# sch_substrate_board_ethernet.net
KiCad netlist of a schematic drawn in Altium Designer
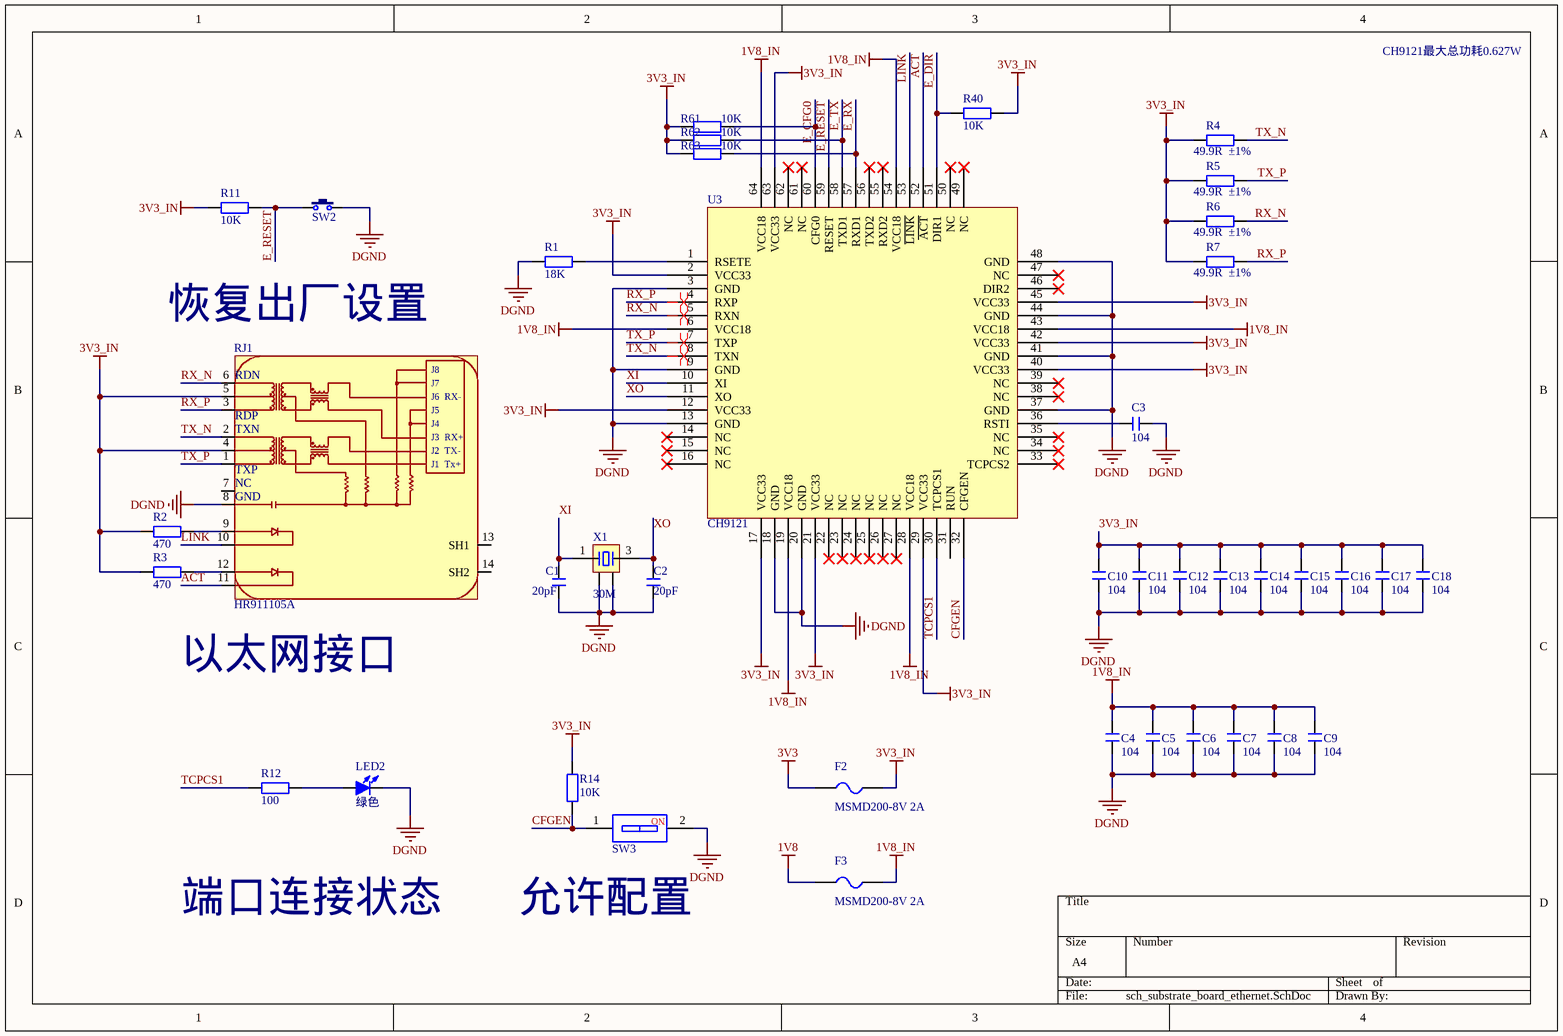
[diagram p0: sch_substrate_board_ethernet.SchDoc]

(export (version "E")
  (design (tool "Eeschema 10.0.6"))
  (components
    (comp (ref "C1")
      (value "20pF")
      (footprint "C 0805_L")
      (description "贴片电容")
      (libsource (lib "0.1 - 电阻-电容-电感") (part "C"))
    )
    (comp (ref "C2")
      (value "20pF")
      (footprint "C 0805_L")
      (description "贴片电容")
      (libsource (lib "0.1 - 电阻-电容-电感") (part "C"))
    )
    (comp (ref "C3")
      (value "104")
      (footprint "C 0805_L")
      (description "贴片电容")
      (libsource (lib "0.1 - 电阻-电容-电感") (part "C"))
    )
    (comp (ref "C4")
      (value "104")
      (footprint "C 0805_L")
      (description "贴片电容")
      (libsource (lib "0.1 - 电阻-电容-电感") (part "C"))
    )
    (comp (ref "C5")
      (value "104")
      (footprint "C 0805_L")
      (description "贴片电容")
      (libsource (lib "0.1 - 电阻-电容-电感") (part "C"))
    )
    (comp (ref "C6")
      (value "104")
      (footprint "C 0805_L")
      (description "贴片电容")
      (libsource (lib "0.1 - 电阻-电容-电感") (part "C"))
    )
    (comp (ref "C7")
      (value "104")
      (footprint "C 0805_L")
      (description "贴片电容")
      (libsource (lib "0.1 - 电阻-电容-电感") (part "C"))
    )
    (comp (ref "C8")
      (value "104")
      (footprint "C 0805_L")
      (description "贴片电容")
      (libsource (lib "0.1 - 电阻-电容-电感") (part "C"))
    )
    (comp (ref "C9")
      (value "104")
      (footprint "C 0805_L")
      (description "贴片电容")
      (libsource (lib "0.1 - 电阻-电容-电感") (part "C"))
    )
    (comp (ref "C10")
      (value "104")
      (footprint "C 0805_L")
      (description "贴片电容")
      (libsource (lib "0.1 - 电阻-电容-电感") (part "C"))
    )
    (comp (ref "C11")
      (value "104")
      (footprint "C 0805_L")
      (description "贴片电容")
      (libsource (lib "0.1 - 电阻-电容-电感") (part "C"))
    )
    (comp (ref "C12")
      (value "104")
      (footprint "C 0805_L")
      (description "贴片电容")
      (libsource (lib "0.1 - 电阻-电容-电感") (part "C"))
    )
    (comp (ref "C13")
      (value "104")
      (footprint "C 0805_L")
      (description "贴片电容")
      (libsource (lib "0.1 - 电阻-电容-电感") (part "C"))
    )
    (comp (ref "C14")
      (value "104")
      (footprint "C 0805_L")
      (description "贴片电容")
      (libsource (lib "0.1 - 电阻-电容-电感") (part "C"))
    )
    (comp (ref "C15")
      (value "104")
      (footprint "C 0805_L")
      (description "贴片电容")
      (libsource (lib "0.1 - 电阻-电容-电感") (part "C"))
    )
    (comp (ref "C16")
      (value "104")
      (footprint "C 0805_L")
      (description "贴片电容")
      (libsource (lib "0.1 - 电阻-电容-电感") (part "C"))
    )
    (comp (ref "C17")
      (value "104")
      (footprint "C 0805_L")
      (description "贴片电容")
      (libsource (lib "0.1 - 电阻-电容-电感") (part "C"))
    )
    (comp (ref "C18")
      (value "104")
      (footprint "C 0805_L")
      (description "贴片电容")
      (libsource (lib "0.1 - 电阻-电容-电感") (part "C"))
    )
    (comp (ref "F2")
      (value "MSMD200-8V 2A")
      (footprint "FU 0603")
      (description "贴片保险丝")
      (fields (field (name "版权归属") "封装库来自淘宝卖家 ID：黄晶宝石"))
      (libsource (lib "2.0 - 保险丝-晶振-光耦") (part "FU"))
    )
    (comp (ref "F3")
      (value "MSMD200-8V 2A")
      (footprint "FU 0603")
      (description "贴片保险丝")
      (fields (field (name "版权归属") "封装库来自淘宝卖家 ID：黄晶宝石"))
      (libsource (lib "2.0 - 保险丝-晶振-光耦") (part "FU"))
    )
    (comp (ref "LED2")
      (value "绿色")
      (footprint "LED 0805G")
      (description "贴片LED")
      (fields (field (name "版权归属") "封装库来自淘宝 ID：黄晶宝石"))
      (libsource (lib "0.3 - LED发光二极管") (part "LED-SMD"))
    )
    (comp (ref "R1")
      (value "18K")
      (footprint "R 0805_L")
      (description "贴片电阻")
      (fields (field (name "版权归属") "来自淘宝 ID：黄晶宝石"))
      (libsource (lib "0.1 - 电阻-电容-电感") (part "R"))
    )
    (comp (ref "R2")
      (value "470")
      (footprint "R 0805_L")
      (description "贴片电阻")
      (fields (field (name "版权归属") "来自淘宝 ID：黄晶宝石"))
      (libsource (lib "0.1 - 电阻-电容-电感") (part "R"))
    )
    (comp (ref "R3")
      (value "470")
      (footprint "R 0805_L")
      (description "贴片电阻")
      (fields (field (name "版权归属") "来自淘宝 ID：黄晶宝石"))
      (libsource (lib "0.1 - 电阻-电容-电感") (part "R"))
    )
    (comp (ref "R4")
      (value "49.9R  ±1%")
      (footprint "R 0603_L")
      (description "贴片电阻")
      (fields (field (name "版权归属") "来自淘宝 ID：黄晶宝石"))
      (libsource (lib "0.1 - 电阻-电容-电感") (part "R"))
    )
    (comp (ref "R5")
      (value "49.9R  ±1%")
      (footprint "R 0603_L")
      (description "贴片电阻")
      (fields (field (name "版权归属") "来自淘宝 ID：黄晶宝石"))
      (libsource (lib "0.1 - 电阻-电容-电感") (part "R"))
    )
    (comp (ref "R6")
      (value "49.9R  ±1%")
      (footprint "R 0603_L")
      (description "贴片电阻")
      (fields (field (name "版权归属") "来自淘宝 ID：黄晶宝石"))
      (libsource (lib "0.1 - 电阻-电容-电感") (part "R"))
    )
    (comp (ref "R7")
      (value "49.9R  ±1%")
      (footprint "R 0603_L")
      (description "贴片电阻")
      (fields (field (name "版权归属") "来自淘宝 ID：黄晶宝石"))
      (libsource (lib "0.1 - 电阻-电容-电感") (part "R"))
    )
    (comp (ref "R11")
      (value "10K")
      (footprint "R 0805_L")
      (description "贴片电阻")
      (fields (field (name "版权归属") "来自淘宝 ID：黄晶宝石"))
      (libsource (lib "0.1 - 电阻-电容-电感") (part "R"))
    )
    (comp (ref "R12")
      (value "100")
      (footprint "R 0805_L")
      (description "贴片电阻")
      (fields (field (name "版权归属") "来自淘宝 ID：黄晶宝石"))
      (libsource (lib "0.1 - 电阻-电容-电感") (part "R"))
    )
    (comp (ref "R14")
      (value "10K")
      (footprint "R 0805_L")
      (description "贴片电阻")
      (fields (field (name "版权归属") "来自淘宝 ID：黄晶宝石"))
      (libsource (lib "0.1 - 电阻-电容-电感") (part "R"))
    )
    (comp (ref "R40")
      (value "10K")
      (footprint "R 0805_L")
      (description "贴片电阻")
      (fields (field (name "版权归属") "来自淘宝 ID：黄晶宝石"))
      (libsource (lib "0.1 - 电阻-电容-电感") (part "R"))
    )
    (comp (ref "R61")
      (value "10K")
      (footprint "R 0805_L")
      (description "贴片电阻")
      (fields (field (name "版权归属") "来自淘宝 ID：黄晶宝石"))
      (libsource (lib "0.1 - 电阻-电容-电感") (part "R"))
    )
    (comp (ref "R62")
      (value "10K")
      (footprint "R 0805_L")
      (description "贴片电阻")
      (fields (field (name "版权归属") "来自淘宝 ID：黄晶宝石"))
      (libsource (lib "0.1 - 电阻-电容-电感") (part "R"))
    )
    (comp (ref "R63")
      (value "10K")
      (footprint "R 0805_L")
      (description "贴片电阻")
      (fields (field (name "版权归属") "来自淘宝 ID：黄晶宝石"))
      (libsource (lib "0.1 - 电阻-电容-电感") (part "R"))
    )
    (comp (ref "RJ1")
      (value "HR911105A")
      (footprint "RJ45")
      (libsource (lib "schlib_substrate") (part "HR911105A"))
    )
    (comp (ref "SW2")
      (value "3x6x5")
      (footprint "TSW SMD-3*6*2.5")
      (description "3x6轻触开关")
      (fields (field (name "版权归属") "封装库来自淘宝 ID：黄晶宝石"))
      (libsource (lib "0.7 - 常用按键-开关") (part "TSW 3x6"))
    )
    (comp (ref "SW3")
      (value "SW-1P")
      (footprint "SW-SMD_DSHP01TSGER")
      (description "1路编码开关")
      (libsource (lib "0.7 - 常用按键-开关") (part "SW-1P"))
    )
    (comp (ref "U3")
      (value "CH9121")
      (footprint "CH9121")
      (description "IC")
      (libsource (lib "schlib_substrate") (part "CH9121"))
    )
    (comp (ref "X1")
      (value "30M")
      (footprint "OSC 3225-4P")
      (description "4脚无源晶振")
      (fields (field (name "版权归属") "封装库来自淘宝卖家 ID：黄晶宝石"))
      (libsource (lib "2.0 - 保险丝-晶振-光耦") (part "XTAL-4P"))
    )
  )
  (nets
    (net (code "1") (name "/ACT") (class "Default")
      (node (ref "RJ1") (pin "11") (pinfunction "11_11") (pintype "passive"))
      (node (ref "U3") (pin "52") (pinfunction "~{ACT}_52") (pintype "passive"))
    )
    (net (code "2") (name "/CFGEN") (class "Default")
      (node (ref "R14") (pin "2") (pinfunction "2_2") (pintype "passive"))
      (node (ref "SW3") (pin "1") (pinfunction "1_1") (pintype "passive"))
      (node (ref "U3") (pin "32") (pinfunction "CFGEN_32") (pintype "passive"))
    )
    (net (code "3") (name "/E_CFG0") (class "Default")
      (node (ref "R61") (pin "1") (pinfunction "1_1") (pintype "passive"))
      (node (ref "U3") (pin "60") (pinfunction "CFG0_60") (pintype "passive"))
    )
    (net (code "4") (name "/E_DIR") (class "Default")
      (node (ref "R40") (pin "1") (pinfunction "1_1") (pintype "passive"))
      (node (ref "U3") (pin "51") (pinfunction "DIR1_51") (pintype "passive"))
    )
    (net (code "5") (name "/E_RESET") (class "Default")
      (node (ref "R11") (pin "1") (pinfunction "1_1") (pintype "passive"))
      (node (ref "SW2") (pin "1") (pinfunction "1_1") (pintype "passive"))
      (node (ref "U3") (pin "59") (pinfunction "RESET_59") (pintype "passive"))
    )
    (net (code "6") (name "/E_RX") (class "Default")
      (node (ref "R63") (pin "1") (pinfunction "1_1") (pintype "passive"))
      (node (ref "U3") (pin "57") (pinfunction "RXD1_57") (pintype "passive"))
    )
    (net (code "7") (name "/E_TX") (class "Default")
      (node (ref "R62") (pin "1") (pinfunction "1_1") (pintype "passive"))
      (node (ref "U3") (pin "58") (pinfunction "TXD1_58") (pintype "passive"))
    )
    (net (code "8") (name "/LINK") (class "Default")
      (node (ref "RJ1") (pin "10") (pinfunction "10_10") (pintype "passive"))
      (node (ref "U3") (pin "53") (pinfunction "~{LINK}_53") (pintype "passive"))
    )
    (net (code "9") (name "/RX_N") (class "Default")
      (node (ref "R6") (pin "2") (pinfunction "2_2") (pintype "passive"))
      (node (ref "RJ1") (pin "6") (pinfunction "RDN_6") (pintype "passive"))
      (node (ref "U3") (pin "5") (pinfunction "RXN_5") (pintype "passive"))
    )
    (net (code "10") (name "/RX_P") (class "Default")
      (node (ref "R7") (pin "2") (pinfunction "2_2") (pintype "passive"))
      (node (ref "RJ1") (pin "3") (pinfunction "RDP_3") (pintype "passive"))
      (node (ref "U3") (pin "4") (pinfunction "RXP_4") (pintype "passive"))
    )
    (net (code "11") (name "/TCPCS1") (class "Default")
      (node (ref "R12") (pin "2") (pinfunction "2_2") (pintype "passive"))
      (node (ref "U3") (pin "30") (pinfunction "TCPCS1_30") (pintype "passive"))
    )
    (net (code "12") (name "/TX_N") (class "Default")
      (node (ref "R4") (pin "2") (pinfunction "2_2") (pintype "passive"))
      (node (ref "RJ1") (pin "2") (pinfunction "TDN_2") (pintype "passive"))
      (node (ref "U3") (pin "8") (pinfunction "TXN_8") (pintype "passive"))
    )
    (net (code "13") (name "/TX_P") (class "Default")
      (node (ref "R5") (pin "2") (pinfunction "2_2") (pintype "passive"))
      (node (ref "RJ1") (pin "1") (pinfunction "TXP_1") (pintype "passive"))
      (node (ref "U3") (pin "7") (pinfunction "TXP_7") (pintype "passive"))
    )
    (net (code "14") (name "/XI") (class "Default")
      (node (ref "C1") (pin "2") (pinfunction "2_2") (pintype "passive"))
      (node (ref "U3") (pin "10") (pinfunction "XI_10") (pintype "passive"))
      (node (ref "X1") (pin "1") (pinfunction "1_1") (pintype "passive"))
    )
    (net (code "15") (name "/XO") (class "Default")
      (node (ref "C2") (pin "2") (pinfunction "2_2") (pintype "passive"))
      (node (ref "U3") (pin "11") (pinfunction "XO_11") (pintype "passive"))
      (node (ref "X1") (pin "3") (pinfunction "3_3") (pintype "passive"))
    )
    (net (code "16") (name "1V8") (class "Default")
      (node (ref "F3") (pin "1") (pinfunction "1_1") (pintype "passive"))
    )
    (net (code "17") (name "1V8_IN") (class "Default")
      (node (ref "C4") (pin "2") (pinfunction "2_2") (pintype "passive"))
      (node (ref "C5") (pin "2") (pinfunction "2_2") (pintype "passive"))
      (node (ref "C6") (pin "2") (pinfunction "2_2") (pintype "passive"))
      (node (ref "C7") (pin "2") (pinfunction "2_2") (pintype "passive"))
      (node (ref "C8") (pin "2") (pinfunction "2_2") (pintype "passive"))
      (node (ref "C9") (pin "2") (pinfunction "2_2") (pintype "passive"))
      (node (ref "F3") (pin "2") (pinfunction "2_2") (pintype "passive"))
      (node (ref "U3") (pin "19") (pinfunction "VCC18_19") (pintype "passive"))
      (node (ref "U3") (pin "28") (pinfunction "VCC18_28") (pintype "passive"))
      (node (ref "U3") (pin "43") (pinfunction "VCC18_43") (pintype "passive"))
      (node (ref "U3") (pin "54") (pinfunction "VCC18_54") (pintype "passive"))
      (node (ref "U3") (pin "6") (pinfunction "VCC18_6") (pintype "passive"))
      (node (ref "U3") (pin "64") (pinfunction "VCC18_64") (pintype "passive"))
    )
    (net (code "18") (name "3V3") (class "Default")
      (node (ref "F2") (pin "1") (pinfunction "1_1") (pintype "passive"))
    )
    (net (code "19") (name "3V3_IN") (class "Default")
      (node (ref "C10") (pin "2") (pinfunction "2_2") (pintype "passive"))
      (node (ref "C11") (pin "2") (pinfunction "2_2") (pintype "passive"))
      (node (ref "C12") (pin "2") (pinfunction "2_2") (pintype "passive"))
      (node (ref "C13") (pin "2") (pinfunction "2_2") (pintype "passive"))
      (node (ref "C14") (pin "2") (pinfunction "2_2") (pintype "passive"))
      (node (ref "C15") (pin "2") (pinfunction "2_2") (pintype "passive"))
      (node (ref "C16") (pin "2") (pinfunction "2_2") (pintype "passive"))
      (node (ref "C17") (pin "2") (pinfunction "2_2") (pintype "passive"))
      (node (ref "C18") (pin "2") (pinfunction "2_2") (pintype "passive"))
      (node (ref "F2") (pin "2") (pinfunction "2_2") (pintype "passive"))
      (node (ref "R11") (pin "2") (pinfunction "2_2") (pintype "passive"))
      (node (ref "R14") (pin "1") (pinfunction "1_1") (pintype "passive"))
      (node (ref "R2") (pin "1") (pinfunction "1_1") (pintype "passive"))
      (node (ref "R3") (pin "1") (pinfunction "1_1") (pintype "passive"))
      (node (ref "R4") (pin "1") (pinfunction "1_1") (pintype "passive"))
      (node (ref "R40") (pin "2") (pinfunction "2_2") (pintype "passive"))
      (node (ref "R5") (pin "1") (pinfunction "1_1") (pintype "passive"))
      (node (ref "R6") (pin "1") (pinfunction "1_1") (pintype "passive"))
      (node (ref "R61") (pin "2") (pinfunction "2_2") (pintype "passive"))
      (node (ref "R62") (pin "2") (pinfunction "2_2") (pintype "passive"))
      (node (ref "R63") (pin "2") (pinfunction "2_2") (pintype "passive"))
      (node (ref "R7") (pin "1") (pinfunction "1_1") (pintype "passive"))
      (node (ref "RJ1") (pin "4") (pinfunction "4_4") (pintype "passive"))
      (node (ref "RJ1") (pin "5") (pintype "passive"))
      (node (ref "U3") (pin "12") (pinfunction "VCC33_12") (pintype "passive"))
      (node (ref "U3") (pin "17") (pinfunction "VCC33_17") (pintype "passive"))
      (node (ref "U3") (pin "2") (pinfunction "VCC33_2") (pintype "passive"))
      (node (ref "U3") (pin "21") (pinfunction "VCC33_21") (pintype "passive"))
      (node (ref "U3") (pin "29") (pinfunction "VCC33_29") (pintype "passive"))
      (node (ref "U3") (pin "40") (pinfunction "VCC33_40") (pintype "passive"))
      (node (ref "U3") (pin "42") (pinfunction "VCC33_42") (pintype "passive"))
      (node (ref "U3") (pin "45") (pinfunction "VCC33_45") (pintype "passive"))
      (node (ref "U3") (pin "63") (pinfunction "VCC33_63") (pintype "passive"))
    )
    (net (code "20") (name "DGND") (class "Default")
      (node (ref "C1") (pin "1") (pinfunction "1_1") (pintype "passive"))
      (node (ref "C10") (pin "1") (pinfunction "1_1") (pintype "passive"))
      (node (ref "C11") (pin "1") (pinfunction "1_1") (pintype "passive"))
      (node (ref "C12") (pin "1") (pinfunction "1_1") (pintype "passive"))
      (node (ref "C13") (pin "1") (pinfunction "1_1") (pintype "passive"))
      (node (ref "C14") (pin "1") (pinfunction "1_1") (pintype "passive"))
      (node (ref "C15") (pin "1") (pinfunction "1_1") (pintype "passive"))
      (node (ref "C16") (pin "1") (pinfunction "1_1") (pintype "passive"))
      (node (ref "C17") (pin "1") (pinfunction "1_1") (pintype "passive"))
      (node (ref "C18") (pin "1") (pinfunction "1_1") (pintype "passive"))
      (node (ref "C2") (pin "1") (pinfunction "1_1") (pintype "passive"))
      (node (ref "C3") (pin "2") (pinfunction "2_2") (pintype "passive"))
      (node (ref "C4") (pin "1") (pinfunction "1_1") (pintype "passive"))
      (node (ref "C5") (pin "1") (pinfunction "1_1") (pintype "passive"))
      (node (ref "C6") (pin "1") (pinfunction "1_1") (pintype "passive"))
      (node (ref "C7") (pin "1") (pinfunction "1_1") (pintype "passive"))
      (node (ref "C8") (pin "1") (pinfunction "1_1") (pintype "passive"))
      (node (ref "C9") (pin "1") (pinfunction "1_1") (pintype "passive"))
      (node (ref "LED2") (pin "2") (pinfunction "K_2") (pintype "passive"))
      (node (ref "R1") (pin "1") (pinfunction "1_1") (pintype "passive"))
      (node (ref "RJ1") (pin "8") (pinfunction "GND_8") (pintype "passive"))
      (node (ref "SW2") (pin "2") (pinfunction "2_2") (pintype "passive"))
      (node (ref "SW3") (pin "2") (pinfunction "2_2") (pintype "passive"))
      (node (ref "U3") (pin "13") (pinfunction "GND_13") (pintype "passive"))
      (node (ref "U3") (pin "18") (pinfunction "GND_18") (pintype "passive"))
      (node (ref "U3") (pin "20") (pinfunction "GND_20") (pintype "passive"))
      (node (ref "U3") (pin "3") (pinfunction "GND_3") (pintype "passive"))
      (node (ref "U3") (pin "37") (pinfunction "GND_37") (pintype "passive"))
      (node (ref "U3") (pin "41") (pinfunction "GND_41") (pintype "passive"))
      (node (ref "U3") (pin "44") (pinfunction "GND_44") (pintype "passive"))
      (node (ref "U3") (pin "48") (pinfunction "GND_48") (pintype "passive"))
      (node (ref "U3") (pin "9") (pinfunction "GND_9") (pintype "passive"))
      (node (ref "X1") (pin "2") (pinfunction "2_2") (pintype "passive"))
      (node (ref "X1") (pin "4") (pinfunction "4_4") (pintype "passive"))
    )
    (net (code "21") (name "Net-(LED2-A)") (class "Default")
      (node (ref "LED2") (pin "1") (pinfunction "A_1") (pintype "passive"))
      (node (ref "R12") (pin "1") (pinfunction "1_1") (pintype "passive"))
    )
    (net (code "22") (name "Net-(R2-Pad2)") (class "Default")
      (node (ref "R2") (pin "2") (pinfunction "2_2") (pintype "passive"))
      (node (ref "RJ1") (pin "9") (pinfunction "9_9") (pintype "passive"))
    )
    (net (code "23") (name "Net-(R3-Pad2)") (class "Default")
      (node (ref "R3") (pin "2") (pinfunction "2_2") (pintype "passive"))
      (node (ref "RJ1") (pin "12") (pinfunction "12_12") (pintype "passive"))
    )
    (net (code "24") (name "Net-(U3-RSETE)") (class "Default")
      (node (ref "R1") (pin "2") (pinfunction "2_2") (pintype "passive"))
      (node (ref "U3") (pin "1") (pinfunction "RSETE_1") (pintype "passive"))
    )
    (net (code "25") (name "Net-(U3-RSTI)") (class "Default")
      (node (ref "C3") (pin "1") (pinfunction "1_1") (pintype "passive"))
      (node (ref "U3") (pin "36") (pinfunction "RSTI_36") (pintype "passive"))
    )
    (net (code "26") (name "unconnected-(RJ1-NC-Pad7)") (class "Default")
      (node (ref "RJ1") (pin "7") (pinfunction "NC_7") (pintype "passive"))
    )
    (net (code "27") (name "unconnected-(RJ1-SH1-Pad13)") (class "Default")
      (node (ref "RJ1") (pin "13") (pinfunction "SH1_13") (pintype "passive"))
    )
    (net (code "28") (name "unconnected-(RJ1-SH2-Pad14)") (class "Default")
      (node (ref "RJ1") (pin "14") (pinfunction "SH2_14") (pintype "passive"))
    )
    (net (code "29") (name "unconnected-(U3-DIR2-Pad46)") (class "Default")
      (node (ref "U3") (pin "46") (pinfunction "DIR2_46") (pintype "passive+no_connect"))
    )
    (net (code "30") (name "unconnected-(U3-NC-Pad14)") (class "Default")
      (node (ref "U3") (pin "14") (pinfunction "NC_14") (pintype "passive+no_connect"))
    )
    (net (code "31") (name "unconnected-(U3-NC-Pad15)") (class "Default")
      (node (ref "U3") (pin "15") (pinfunction "NC_15") (pintype "passive+no_connect"))
    )
    (net (code "32") (name "unconnected-(U3-NC-Pad16)") (class "Default")
      (node (ref "U3") (pin "16") (pinfunction "NC_16") (pintype "passive+no_connect"))
    )
    (net (code "33") (name "unconnected-(U3-NC-Pad22)") (class "Default")
      (node (ref "U3") (pin "22") (pinfunction "NC_22") (pintype "passive+no_connect"))
    )
    (net (code "34") (name "unconnected-(U3-NC-Pad23)") (class "Default")
      (node (ref "U3") (pin "23") (pinfunction "NC_23") (pintype "passive+no_connect"))
    )
    (net (code "35") (name "unconnected-(U3-NC-Pad24)") (class "Default")
      (node (ref "U3") (pin "24") (pinfunction "NC_24") (pintype "passive+no_connect"))
    )
    (net (code "36") (name "unconnected-(U3-NC-Pad25)") (class "Default")
      (node (ref "U3") (pin "25") (pinfunction "NC_25") (pintype "passive+no_connect"))
    )
    (net (code "37") (name "unconnected-(U3-NC-Pad26)") (class "Default")
      (node (ref "U3") (pin "26") (pinfunction "NC_26") (pintype "passive+no_connect"))
    )
    (net (code "38") (name "unconnected-(U3-NC-Pad27)") (class "Default")
      (node (ref "U3") (pin "27") (pinfunction "NC_27") (pintype "passive+no_connect"))
    )
    (net (code "39") (name "unconnected-(U3-NC-Pad34)") (class "Default")
      (node (ref "U3") (pin "34") (pinfunction "NC_34") (pintype "passive+no_connect"))
    )
    (net (code "40") (name "unconnected-(U3-NC-Pad35)") (class "Default")
      (node (ref "U3") (pin "35") (pinfunction "NC_35") (pintype "passive+no_connect"))
    )
    (net (code "41") (name "unconnected-(U3-NC-Pad38)") (class "Default")
      (node (ref "U3") (pin "38") (pinfunction "NC_38") (pintype "passive+no_connect"))
    )
    (net (code "42") (name "unconnected-(U3-NC-Pad39)") (class "Default")
      (node (ref "U3") (pin "39") (pinfunction "NC_39") (pintype "passive+no_connect"))
    )
    (net (code "43") (name "unconnected-(U3-NC-Pad47)") (class "Default")
      (node (ref "U3") (pin "47") (pinfunction "NC_47") (pintype "passive+no_connect"))
    )
    (net (code "44") (name "unconnected-(U3-NC-Pad49)") (class "Default")
      (node (ref "U3") (pin "49") (pinfunction "NC_49") (pintype "passive+no_connect"))
    )
    (net (code "45") (name "unconnected-(U3-NC-Pad50)") (class "Default")
      (node (ref "U3") (pin "50") (pinfunction "NC_50") (pintype "passive+no_connect"))
    )
    (net (code "46") (name "unconnected-(U3-NC-Pad61)") (class "Default")
      (node (ref "U3") (pin "61") (pinfunction "NC_61") (pintype "passive+no_connect"))
    )
    (net (code "47") (name "unconnected-(U3-NC-Pad62)") (class "Default")
      (node (ref "U3") (pin "62") (pinfunction "NC_62") (pintype "passive+no_connect"))
    )
    (net (code "48") (name "unconnected-(U3-RUN-Pad31)") (class "Default")
      (node (ref "U3") (pin "31") (pinfunction "RUN_31") (pintype "passive"))
    )
    (net (code "49") (name "unconnected-(U3-RXD2-Pad55)") (class "Default")
      (node (ref "U3") (pin "55") (pinfunction "RXD2_55") (pintype "passive+no_connect"))
    )
    (net (code "50") (name "unconnected-(U3-TCPCS2-Pad33)") (class "Default")
      (node (ref "U3") (pin "33") (pinfunction "TCPCS2_33") (pintype "passive+no_connect"))
    )
    (net (code "51") (name "unconnected-(U3-TXD2-Pad56)") (class "Default")
      (node (ref "U3") (pin "56") (pinfunction "TXD2_56") (pintype "passive+no_connect"))
    )
  )
)
